# HeartAware_AnalogSensorControl.net
KiCad netlist of a schematic drawn in Altium Designer
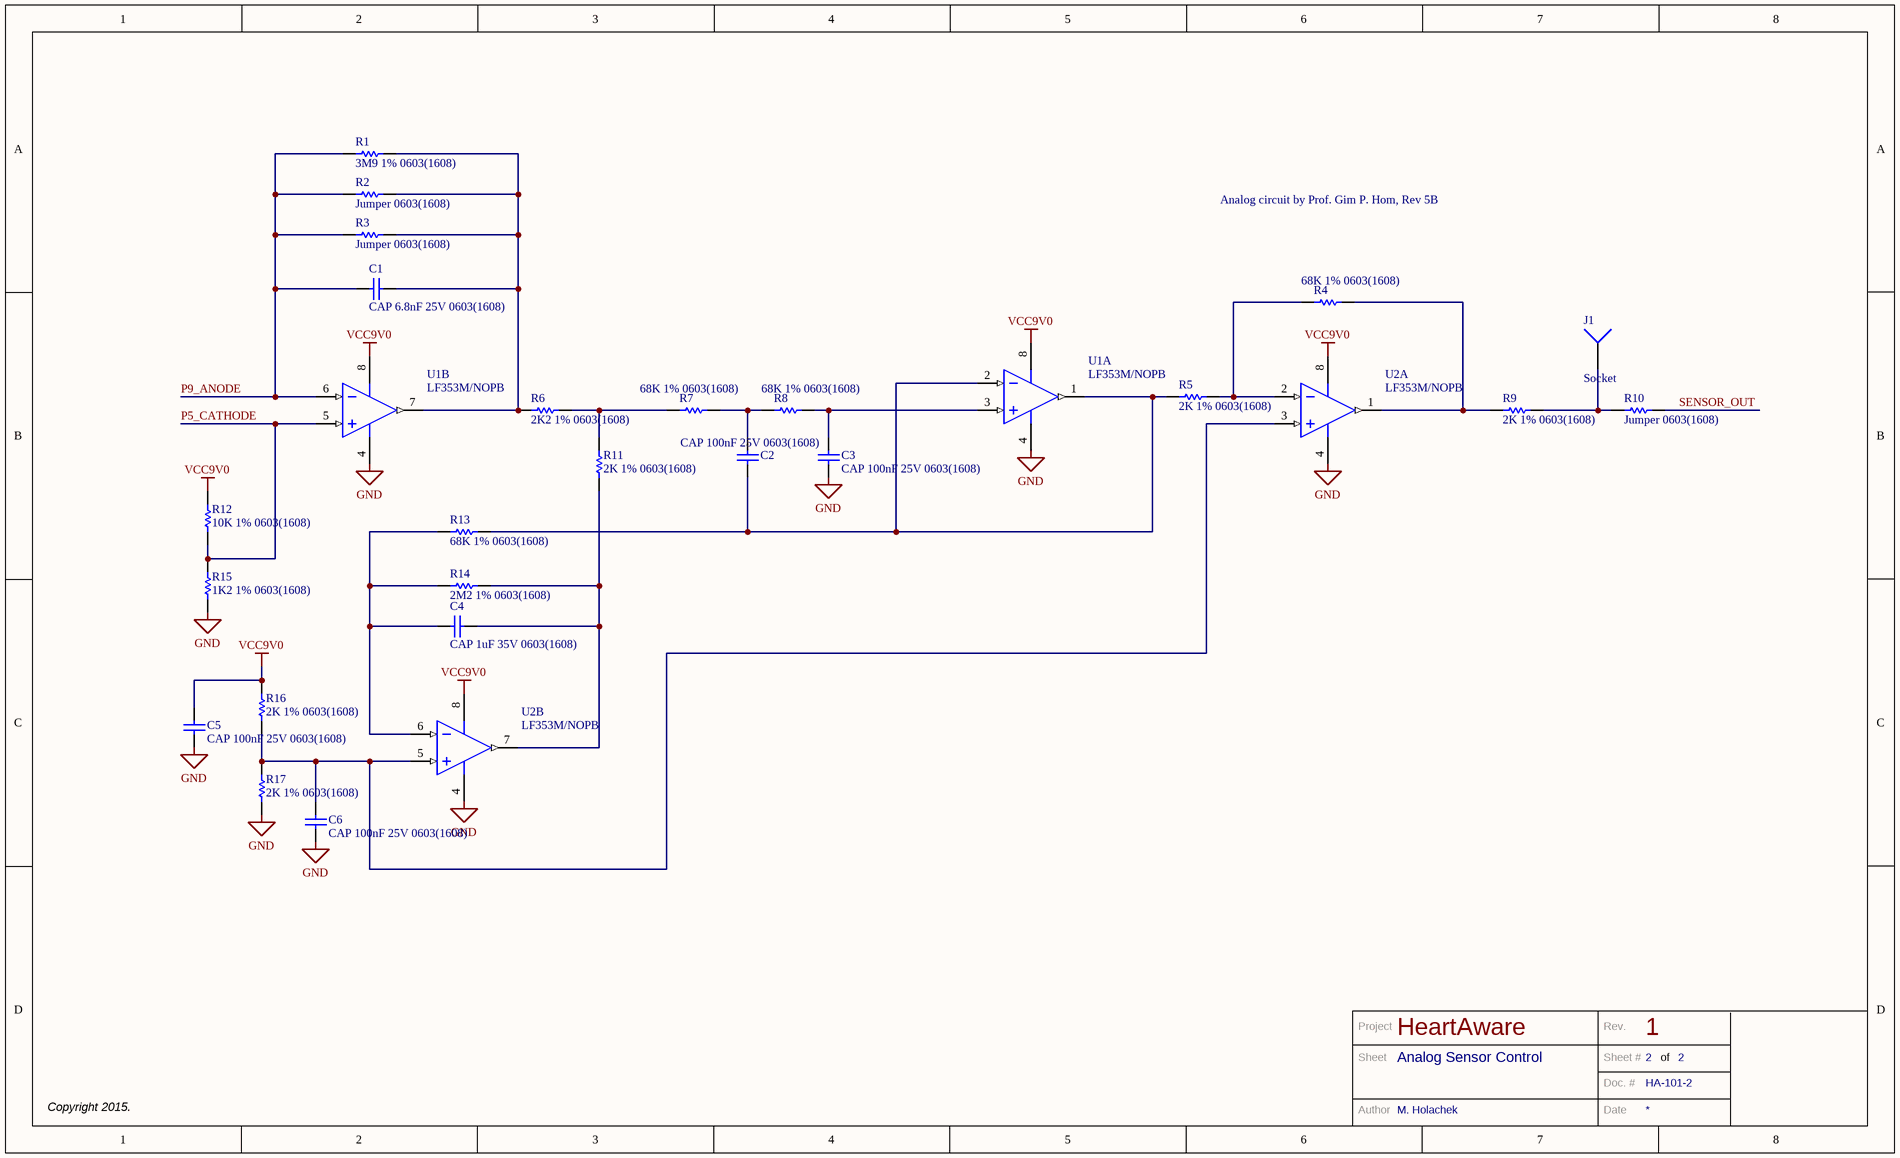
[diagram p0: HeartAware_AnalogSensorControl.SchDoc]

(export (version "E")
  (design (tool "Eeschema 10.0.6"))
  (components
    (comp (ref "C1")
      (value "CAP 6.8nF 25V 0603(1608)")
      (footprint "CAPC0603(1608)100_N")
      (description "CAP 6.8nF 25V Â±20% 0603 (1608 Metric) Thickness 1mm SMD")
      (fields (field (name "TOLERANCE") "Â±20%"))
      (libsource (lib "Altium Content Vault") (part "CAP"))
    )
    (comp (ref "C2")
      (value "CAP 100nF 25V 0603(1608)")
      (footprint "CAPC0603(1608)100_M")
      (description "CAP 100nF 25V Â±10% 0603 (1608 Metric) Thickness 1mm SMD")
      (fields (field (name "TOLERANCE") "Â±10%"))
      (libsource (lib "Altium Content Vault") (part "CAP"))
    )
    (comp (ref "C3")
      (value "CAP 100nF 25V 0603(1608)")
      (footprint "CAPC0603(1608)100_M")
      (description "CAP 100nF 25V Â±10% 0603 (1608 Metric) Thickness 1mm SMD")
      (fields (field (name "TOLERANCE") "Â±10%"))
      (libsource (lib "Altium Content Vault") (part "CAP"))
    )
    (comp (ref "C4")
      (value "CAP 1uF 35V 0603(1608)")
      (footprint "CAPC0603(1608)100_L")
      (description "CAP 1uF 35V Â±10% 0603 (1608 Metric) Thickness 1mm SMD")
      (fields (field (name "TOLERANCE") "Â±10%"))
      (libsource (lib "Altium Content Vault") (part "CAP"))
    )
    (comp (ref "C5")
      (value "CAP 100nF 25V 0603(1608)")
      (footprint "CAPC0603(1608)100_M")
      (description "CAP 100nF 25V Â±10% 0603 (1608 Metric) Thickness 1mm SMD")
      (fields (field (name "TOLERANCE") "Â±10%"))
      (libsource (lib "Altium Content Vault") (part "CAP"))
    )
    (comp (ref "C6")
      (value "CAP 100nF 25V 0603(1608)")
      (footprint "CAPC0603(1608)100_M")
      (description "CAP 100nF 25V Â±10% 0603 (1608 Metric) Thickness 1mm SMD")
      (fields (field (name "TOLERANCE") "Â±10%"))
      (libsource (lib "Altium Content Vault") (part "CAP"))
    )
    (comp (ref "J1")
      (value "Socket")
      (footprint "PIN1")
      (fields (field (name "PUBLISHER") "Altium Limited"))
      (libsource (lib "Miscellaneous Connectors") (part "Socket"))
    )
    (comp (ref "R1")
      (value "3M9 1% 0603(1608)")
      (footprint "RESC0603(1608)_M")
      (description "3M9 0.1W 1% 0603 (1608 Metric)  SMD")
      (fields (field (name "POWER") "0.1 W") (field (name "TOLERANCE") "1 %"))
      (libsource (lib "Altium Content Vault") (part "RES"))
    )
    (comp (ref "R2")
      (value "Jumper 0603(1608)")
      (footprint "RESC0603(1608)_N")
      (description "Jumper 0603 (1608 Metric)")
      (fields (field (name "POWER") "None"))
      (libsource (lib "Altium Content Vault") (part "RES"))
    )
    (comp (ref "R3")
      (value "Jumper 0603(1608)")
      (footprint "RESC0603(1608)_N")
      (description "Jumper 0603 (1608 Metric)")
      (fields (field (name "POWER") "None"))
      (libsource (lib "Altium Content Vault") (part "RES"))
    )
    (comp (ref "R4")
      (value "68K 1% 0603(1608)")
      (footprint "RESC0603(1608)_M")
      (description "68K 0.1W 1% 0603 (1608 Metric)  SMD")
      (fields (field (name "POWER") "0.1 W") (field (name "TOLERANCE") "1 %"))
      (libsource (lib "Altium Content Vault") (part "RES"))
    )
    (comp (ref "R5")
      (value "2K 1% 0603(1608)")
      (footprint "RESC0603(1608)_N")
      (description "2K 0.1W 1% 0603 (1608 Metric)  SMD")
      (fields (field (name "POWER") "0.1 W") (field (name "TOLERANCE") "1 %"))
      (libsource (lib "Altium Content Vault") (part "RES"))
    )
    (comp (ref "R6")
      (value "2K2 1% 0603(1608)")
      (footprint "RESC0603(1608)_L")
      (description "2K2 0.1W 1% 0603 (1608 Metric)  SMD")
      (fields (field (name "TOLERANCE") "1 %") (field (name "POWER") "0.1 W"))
      (libsource (lib "Altium Content Vault") (part "RES"))
    )
    (comp (ref "R7")
      (value "68K 1% 0603(1608)")
      (footprint "RESC0603(1608)_M")
      (description "68K 0.1W 1% 0603 (1608 Metric)  SMD")
      (fields (field (name "POWER") "0.1 W") (field (name "TOLERANCE") "1 %"))
      (libsource (lib "Altium Content Vault") (part "RES"))
    )
    (comp (ref "R8")
      (value "68K 1% 0603(1608)")
      (footprint "RESC0603(1608)_M")
      (description "68K 0.1W 1% 0603 (1608 Metric)  SMD")
      (fields (field (name "POWER") "0.1 W") (field (name "TOLERANCE") "1 %"))
      (libsource (lib "Altium Content Vault") (part "RES"))
    )
    (comp (ref "R9")
      (value "2K 1% 0603(1608)")
      (footprint "RESC0603(1608)_N")
      (description "2K 0.1W 1% 0603 (1608 Metric)  SMD")
      (fields (field (name "POWER") "0.1 W") (field (name "TOLERANCE") "1 %"))
      (libsource (lib "Altium Content Vault") (part "RES"))
    )
    (comp (ref "R10")
      (value "Jumper 0603(1608)")
      (footprint "RESC0603(1608)_N")
      (description "Jumper 0603 (1608 Metric)")
      (fields (field (name "POWER") "None"))
      (libsource (lib "Altium Content Vault") (part "RES"))
    )
    (comp (ref "R11")
      (value "2K 1% 0603(1608)")
      (footprint "RESC0603(1608)_N")
      (description "2K 0.1W 1% 0603 (1608 Metric)  SMD")
      (fields (field (name "POWER") "0.1 W") (field (name "TOLERANCE") "1 %"))
      (libsource (lib "Altium Content Vault") (part "RES"))
    )
    (comp (ref "R12")
      (value "10K 1% 0603(1608)")
      (footprint "RESC0603(1608)_N")
      (description "10K 0.1W 1% 0603 (1608 Metric)  SMD")
      (fields (field (name "POWER") "0.1 W") (field (name "TOLERANCE") "1 %"))
      (libsource (lib "Altium Content Vault") (part "RES"))
    )
    (comp (ref "R13")
      (value "68K 1% 0603(1608)")
      (footprint "RESC0603(1608)_M")
      (description "68K 0.1W 1% 0603 (1608 Metric)  SMD")
      (fields (field (name "POWER") "0.1 W") (field (name "TOLERANCE") "1 %"))
      (libsource (lib "Altium Content Vault") (part "RES"))
    )
    (comp (ref "R14")
      (value "2M2 1% 0603(1608)")
      (footprint "RESC0603(1608)_M")
      (description "2M2 0.1W 1% 0603 (1608 Metric)  SMD")
      (fields (field (name "TOLERANCE") "1 %") (field (name "POWER") "0.1 W"))
      (libsource (lib "Altium Content Vault") (part "RES"))
    )
    (comp (ref "R15")
      (value "1K2 1% 0603(1608)")
      (footprint "RESC0603(1608)_M")
      (description "1K2 0.1W 1% 0603 (1608 Metric)  SMD")
      (fields (field (name "POWER") "0.1 W") (field (name "TOLERANCE") "1 %"))
      (libsource (lib "Altium Content Vault") (part "RES"))
    )
    (comp (ref "R16")
      (value "2K 1% 0603(1608)")
      (footprint "RESC0603(1608)_N")
      (description "2K 0.1W 1% 0603 (1608 Metric)  SMD")
      (fields (field (name "POWER") "0.1 W") (field (name "TOLERANCE") "1 %"))
      (libsource (lib "Altium Content Vault") (part "RES"))
    )
    (comp (ref "R17")
      (value "2K 1% 0603(1608)")
      (footprint "RESC0603(1608)_N")
      (description "2K 0.1W 1% 0603 (1608 Metric)  SMD")
      (fields (field (name "POWER") "0.1 W") (field (name "TOLERANCE") "1 %"))
      (libsource (lib "Altium Content Vault") (part "RES"))
    )
    (comp (ref "U1")
      (value "LF353M/NOPB")
      (footprint "M08A_M")
      (description "Wide Bandwidth Dual JFET Input Operational Amplifier, 8-pin Narrow SOIC, Pb-Free")
      (fields (field (name "MANUFACTURER") "National Semiconductor"))
      (libsource (lib "Altium Content Vault") (part "AMP-OPA-LF353-8"))
    )
    (comp (ref "U2")
      (value "LF353M/NOPB")
      (footprint "M08A_M")
      (description "Wide Bandwidth Dual JFET Input Operational Amplifier, 8-pin Narrow SOIC, Pb-Free")
      (fields (field (name "MANUFACTURER") "National Semiconductor"))
      (libsource (lib "Altium Content Vault") (part "AMP-OPA-LF353-8"))
    )
  )
  (nets
    (net (code "1") (name "/P5_CATHODE") (class "Default")
      (node (ref "R12") (pin "2") (pinfunction "2_2") (pintype "passive"))
      (node (ref "R15") (pin "2") (pinfunction "2_2") (pintype "passive"))
      (node (ref "U1") (pin "5") (pinfunction "INB+_5") (pintype "input"))
    )
    (net (code "2") (name "/P9_ANODE") (class "Default")
      (node (ref "C1") (pin "1") (pinfunction "1_1") (pintype "passive"))
      (node (ref "R1") (pin "1") (pinfunction "1_1") (pintype "passive"))
      (node (ref "R2") (pin "1") (pinfunction "1_1") (pintype "passive"))
      (node (ref "R3") (pin "1") (pinfunction "1_1") (pintype "passive"))
      (node (ref "U1") (pin "6") (pinfunction "INB-_6") (pintype "input"))
    )
    (net (code "3") (name "/SENSOR_OUT") (class "Default")
      (node (ref "R10") (pin "2") (pinfunction "2_2") (pintype "passive"))
    )
    (net (code "4") (name "GND") (class "Default")
      (node (ref "C3") (pin "1") (pinfunction "1_1") (pintype "passive"))
      (node (ref "C5") (pin "1") (pinfunction "1_1") (pintype "passive"))
      (node (ref "C6") (pin "1") (pinfunction "1_1") (pintype "passive"))
      (node (ref "R15") (pin "1") (pinfunction "1_1") (pintype "passive"))
      (node (ref "R17") (pin "1") (pinfunction "1_1") (pintype "passive"))
      (node (ref "U1") (pin "4") (pinfunction "V-_4") (pintype "power_in"))
      (node (ref "U2") (pin "4") (pinfunction "V-_4") (pintype "power_in"))
    )
    (net (code "5") (name "Net-(C2-Pad2)") (class "Default")
      (node (ref "C2") (pin "2") (pinfunction "2_2") (pintype "passive"))
      (node (ref "R7") (pin "2") (pinfunction "2_2") (pintype "passive"))
      (node (ref "R8") (pin "1") (pinfunction "1_1") (pintype "passive"))
    )
    (net (code "6") (name "Net-(J1-Pad1)") (class "Default")
      (node (ref "J1") (pin "1") (pinfunction "1_1") (pintype "passive"))
      (node (ref "R10") (pin "1") (pinfunction "1_1") (pintype "passive"))
      (node (ref "R9") (pin "2") (pinfunction "2_2") (pintype "passive"))
    )
    (net (code "7") (name "Net-(R11-Pad2)") (class "Default")
      (node (ref "R11") (pin "2") (pinfunction "2_2") (pintype "passive"))
      (node (ref "R6") (pin "2") (pinfunction "2_2") (pintype "passive"))
      (node (ref "R7") (pin "1") (pinfunction "1_1") (pintype "passive"))
    )
    (net (code "8") (name "Net-(U1A-INA+)") (class "Default")
      (node (ref "C3") (pin "2") (pinfunction "2_2") (pintype "passive"))
      (node (ref "R8") (pin "2") (pinfunction "2_2") (pintype "passive"))
      (node (ref "U1") (pin "3") (pinfunction "INA+_3") (pintype "input"))
    )
    (net (code "9") (name "Net-(U1A-INA-)") (class "Default")
      (node (ref "C2") (pin "1") (pinfunction "1_1") (pintype "passive"))
      (node (ref "R13") (pin "1") (pinfunction "1_1") (pintype "passive"))
      (node (ref "R5") (pin "1") (pinfunction "1_1") (pintype "passive"))
      (node (ref "U1") (pin "1") (pinfunction "OUTA_1") (pintype "output"))
      (node (ref "U1") (pin "2") (pinfunction "INA-_2") (pintype "input"))
    )
    (net (code "10") (name "Net-(U1B-OUTB)") (class "Default")
      (node (ref "C1") (pin "2") (pinfunction "2_2") (pintype "passive"))
      (node (ref "R1") (pin "2") (pinfunction "2_2") (pintype "passive"))
      (node (ref "R2") (pin "2") (pinfunction "2_2") (pintype "passive"))
      (node (ref "R3") (pin "2") (pinfunction "2_2") (pintype "passive"))
      (node (ref "R6") (pin "1") (pinfunction "1_1") (pintype "passive"))
      (node (ref "U1") (pin "7") (pinfunction "OUTB_7") (pintype "output"))
    )
    (net (code "11") (name "Net-(U2A-INA+)") (class "Default")
      (node (ref "C6") (pin "2") (pinfunction "2_2") (pintype "passive"))
      (node (ref "R16") (pin "1") (pinfunction "1_1") (pintype "passive"))
      (node (ref "R17") (pin "2") (pinfunction "2_2") (pintype "passive"))
      (node (ref "U2") (pin "3") (pinfunction "INA+_3") (pintype "input"))
      (node (ref "U2") (pin "5") (pinfunction "INB+_5") (pintype "input"))
    )
    (net (code "12") (name "Net-(U2A-INA-)") (class "Default")
      (node (ref "R4") (pin "1") (pinfunction "1_1") (pintype "passive"))
      (node (ref "R5") (pin "2") (pinfunction "2_2") (pintype "passive"))
      (node (ref "U2") (pin "2") (pinfunction "INA-_2") (pintype "input"))
    )
    (net (code "13") (name "Net-(U2A-OUTA)") (class "Default")
      (node (ref "R4") (pin "2") (pinfunction "2_2") (pintype "passive"))
      (node (ref "R9") (pin "1") (pinfunction "1_1") (pintype "passive"))
      (node (ref "U2") (pin "1") (pinfunction "OUTA_1") (pintype "output"))
    )
    (net (code "14") (name "Net-(U2B-INB-)") (class "Default")
      (node (ref "C4") (pin "1") (pinfunction "1_1") (pintype "passive"))
      (node (ref "R13") (pin "2") (pinfunction "2_2") (pintype "passive"))
      (node (ref "R14") (pin "1") (pinfunction "1_1") (pintype "passive"))
      (node (ref "U2") (pin "6") (pinfunction "INB-_6") (pintype "input"))
    )
    (net (code "15") (name "Net-(U2B-OUTB)") (class "Default")
      (node (ref "C4") (pin "2") (pinfunction "2_2") (pintype "passive"))
      (node (ref "R11") (pin "1") (pinfunction "1_1") (pintype "passive"))
      (node (ref "R14") (pin "2") (pinfunction "2_2") (pintype "passive"))
      (node (ref "U2") (pin "7") (pinfunction "OUTB_7") (pintype "output"))
    )
    (net (code "16") (name "VCC9V0") (class "Default")
      (node (ref "C5") (pin "2") (pinfunction "2_2") (pintype "passive"))
      (node (ref "R12") (pin "1") (pinfunction "1_1") (pintype "passive"))
      (node (ref "R16") (pin "2") (pinfunction "2_2") (pintype "passive"))
      (node (ref "U1") (pin "8") (pinfunction "V+_8") (pintype "power_in"))
      (node (ref "U2") (pin "8") (pinfunction "V+_8") (pintype "power_in"))
    )
  )
)
